# updi_programmer.net
KiCad netlist of a schematic drawn in EAGLE
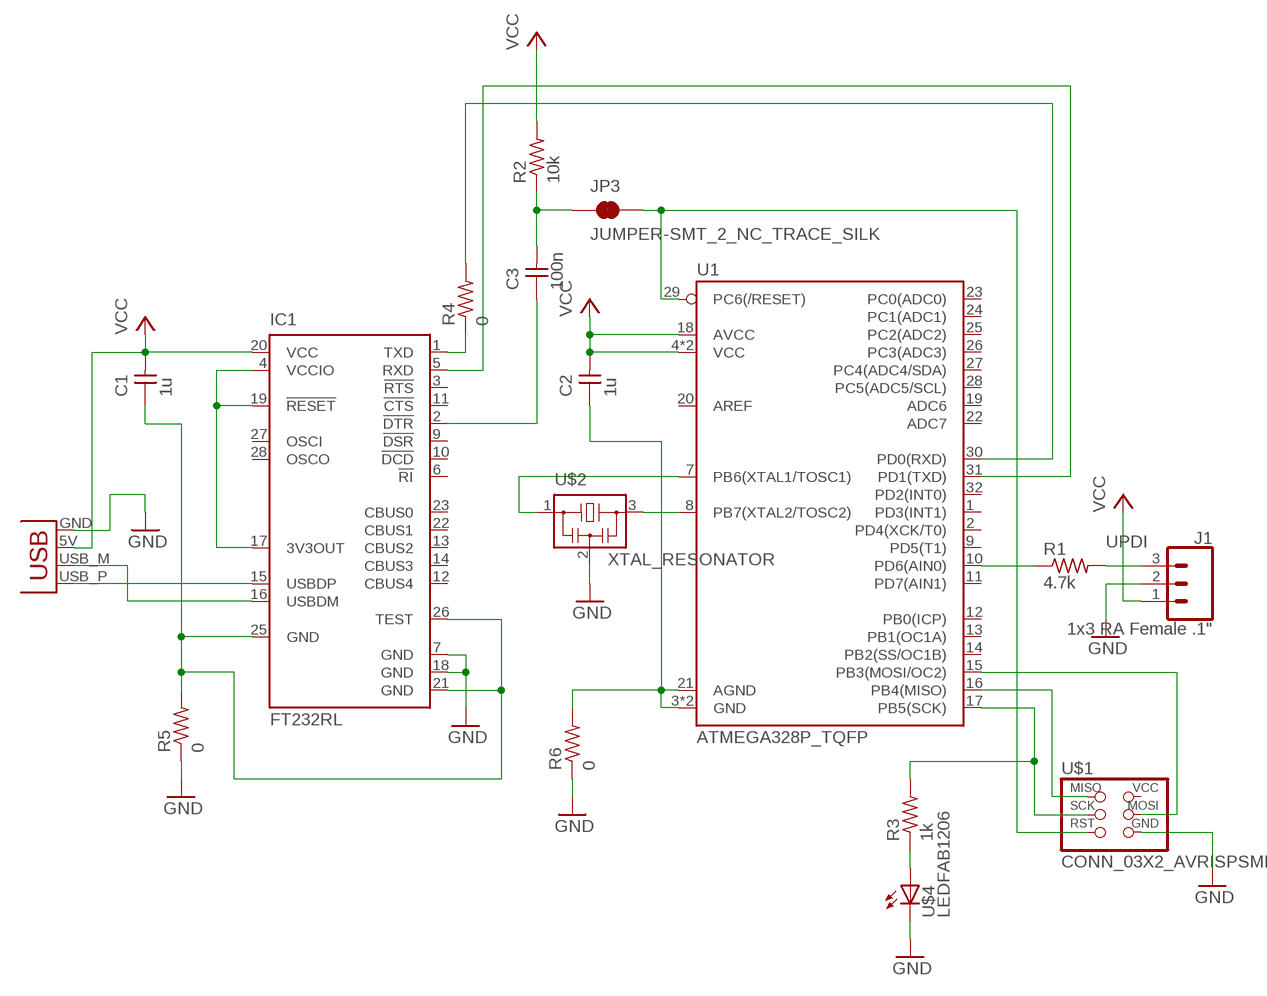
[diagram p0: schematic, sheet 1]

(export (version "E")
  (design (tool "Eeschema 10.0.6"))
  (components
    (comp (ref "C1")
      (value "1u")
      (footprint "eagle-import:C1206FAB")
      (libsource (lib "eagle-import") (part "CAP_UNPOLARIZEDFAB"))
    )
    (comp (ref "C2")
      (value "1u")
      (footprint "eagle-import:C1206FAB")
      (libsource (lib "eagle-import") (part "CAP_UNPOLARIZEDFAB"))
    )
    (comp (ref "C3")
      (value "100n")
      (footprint "eagle-import:C1206FAB")
      (libsource (lib "eagle-import") (part "CAP_UNPOLARIZEDFAB"))
    )
    (comp (ref "IC1")
      (value "FT232RL")
      (footprint "eagle-import:SSOP28")
      (libsource (lib "eagle-import") (part "FT232RL"))
    )
    (comp (ref "J1")
      (value "1x3 RA Female .1\"")
      (footprint "eagle-import:1X03_SMD_RA_FEMALE")
      (libsource (lib "eagle-import") (part "CONN_03SMD_RA_FEMALE"))
    )
    (comp (ref "JP3")
      (value "JUMPER-SMT_2_NC_TRACE_SILK")
      (footprint "eagle-import:SMT-JUMPER_2_NC_TRACE_SILK")
      (libsource (lib "eagle-import") (part "JUMPER-SMT_2_NC_TRACE_SILK"))
    )
    (comp (ref "R1")
      (value "4.7k")
      (footprint "eagle-import:R1206FAB")
      (libsource (lib "eagle-import") (part "R1206FAB"))
    )
    (comp (ref "R2")
      (value "10k")
      (footprint "eagle-import:R1206FAB")
      (libsource (lib "eagle-import") (part "R1206FAB"))
    )
    (comp (ref "R3")
      (value "1k")
      (footprint "eagle-import:R1206FAB")
      (libsource (lib "eagle-import") (part "R1206FAB"))
    )
    (comp (ref "R4")
      (value "0")
      (footprint "eagle-import:R1206FAB")
      (libsource (lib "eagle-import") (part "R1206FAB"))
    )
    (comp (ref "R5")
      (value "0")
      (footprint "eagle-import:R1206FAB")
      (libsource (lib "eagle-import") (part "R1206FAB"))
    )
    (comp (ref "R6")
      (value "0")
      (footprint "eagle-import:R1206FAB")
      (libsource (lib "eagle-import") (part "R1206FAB"))
    )
    (comp (ref "U$1")
      (value "CONN_03X2_AVRISPSMD")
      (footprint "eagle-import:2X03SMD")
      (libsource (lib "eagle-import") (part "CONN_03X2_AVRISPSMD"))
    )
    (comp (ref "U$2")
      (value "XTAL_RESONATOR")
      (footprint "eagle-import:EFOBM")
      (libsource (lib "eagle-import") (part "XTAL_RESONATOR"))
    )
    (comp (ref "U$4")
      (value "LEDFAB1206")
      (footprint "eagle-import:LED1206FAB")
      (libsource (lib "eagle-import") (part "LEDFAB1206"))
    )
    (comp (ref "U1")
      (value "ATMEGA328P_TQFP")
      (footprint "eagle-import:TQFP32-08")
      (libsource (lib "eagle-import") (part "ATMEGA328P_TQFP"))
    )
    (comp (ref "X1")
      (value "CONN_USBPCB")
      (footprint "eagle-import:USB-A-PCB")
      (libsource (lib "eagle-import") (part "CONN_USBPCB"))
    )
  )
  (nets
    (net (code "1") (name "/UPDI") (class "Default")
      (node (ref "J1") (pin "3") (pinfunction "3_3") (pintype "passive"))
      (node (ref "R1") (pin "2") (pinfunction "2_2") (pintype "passive"))
    )
    (net (code "2") (name "GND") (class "Default")
      (node (ref "IC1") (pin "18") (pinfunction "GND_18") (pintype "power_in"))
      (node (ref "IC1") (pin "7") (pinfunction "GND_7") (pintype "power_in"))
      (node (ref "J1") (pin "2") (pinfunction "2_2") (pintype "passive"))
      (node (ref "R5") (pin "1") (pinfunction "1_1") (pintype "passive"))
      (node (ref "R6") (pin "1") (pinfunction "1_1") (pintype "passive"))
      (node (ref "U$1") (pin "6") (pinfunction "GND_6") (pintype "passive"))
      (node (ref "U$2") (pin "2") (pinfunction "2_2") (pintype "passive"))
      (node (ref "U$4") (pin "2") (pinfunction "C_2") (pintype "passive"))
      (node (ref "X1") (pin "GND") (pinfunction "GND_GND") (pintype "bidirectional"))
    )
    (net (code "3") (name "Net-(C3-Pad2)") (class "Default")
      (node (ref "C3") (pin "2") (pinfunction "2_2") (pintype "passive"))
      (node (ref "JP3") (pin "1") (pinfunction "1_1") (pintype "passive"))
      (node (ref "R2") (pin "1") (pinfunction "1_1") (pintype "passive"))
    )
    (net (code "4") (name "Net-(IC1-3V3OUT)") (class "Default")
      (node (ref "IC1") (pin "17") (pinfunction "3V3OUT_17") (pintype "output"))
      (node (ref "IC1") (pin "19") (pinfunction "~{RESET}_19") (pintype "input"))
      (node (ref "IC1") (pin "4") (pinfunction "VCCIO_4") (pintype "power_in"))
    )
    (net (code "5") (name "Net-(IC1-RXD)") (class "Default")
      (node (ref "IC1") (pin "5") (pinfunction "RXD_5") (pintype "input"))
      (node (ref "U1") (pin "31") (pinfunction "PD1(TXD)_31") (pintype "bidirectional"))
    )
    (net (code "6") (name "Net-(IC1-TEST)") (class "Default")
      (node (ref "C1") (pin "1") (pinfunction "1_1") (pintype "passive"))
      (node (ref "IC1") (pin "21") (pinfunction "GND_21") (pintype "power_in"))
      (node (ref "IC1") (pin "25") (pinfunction "GND_25") (pintype "power_in"))
      (node (ref "IC1") (pin "26") (pinfunction "TEST_26") (pintype "input"))
      (node (ref "R5") (pin "2") (pinfunction "2_2") (pintype "passive"))
    )
    (net (code "7") (name "Net-(IC1-TXD)") (class "Default")
      (node (ref "IC1") (pin "1") (pinfunction "TXD_1") (pintype "output"))
      (node (ref "R4") (pin "1") (pinfunction "1_1") (pintype "passive"))
    )
    (net (code "8") (name "Net-(IC1-USBDM)") (class "Default")
      (node (ref "IC1") (pin "16") (pinfunction "USBDM_16") (pintype "bidirectional"))
      (node (ref "X1") (pin "USB_M") (pinfunction "D-_USB_M") (pintype "bidirectional"))
    )
    (net (code "9") (name "Net-(IC1-USBDP)") (class "Default")
      (node (ref "IC1") (pin "15") (pinfunction "USBDP_15") (pintype "bidirectional"))
      (node (ref "X1") (pin "USB_P") (pinfunction "D+_USB_P") (pintype "bidirectional"))
    )
    (net (code "10") (name "Net-(IC1-~{DTR})") (class "Default")
      (node (ref "C3") (pin "1") (pinfunction "1_1") (pintype "passive"))
      (node (ref "IC1") (pin "2") (pinfunction "~{DTR}_2") (pintype "output"))
    )
    (net (code "11") (name "Net-(U$1-MISO)") (class "Default")
      (node (ref "U$1") (pin "1") (pinfunction "MISO_1") (pintype "passive"))
      (node (ref "U1") (pin "16") (pinfunction "PB4(MISO)_16") (pintype "bidirectional"))
    )
    (net (code "12") (name "Net-(U$1-MOSI)") (class "Default")
      (node (ref "U$1") (pin "4") (pinfunction "MOSI_4") (pintype "passive"))
      (node (ref "U1") (pin "15") (pinfunction "PB3(MOSI/OC2)_15") (pintype "bidirectional"))
    )
    (net (code "13") (name "Net-(U$1-RST)") (class "Default")
      (node (ref "JP3") (pin "2") (pinfunction "2_2") (pintype "passive"))
      (node (ref "U$1") (pin "5") (pinfunction "RST_5") (pintype "passive"))
      (node (ref "U1") (pin "29") (pinfunction "PC6(/RESET)_29") (pintype "bidirectional"))
    )
    (net (code "14") (name "Net-(U$1-SCK)") (class "Default")
      (node (ref "R3") (pin "2") (pinfunction "2_2") (pintype "passive"))
      (node (ref "U$1") (pin "3") (pinfunction "SCK_3") (pintype "passive"))
      (node (ref "U1") (pin "17") (pinfunction "PB5(SCK)_17") (pintype "bidirectional"))
    )
    (net (code "15") (name "Net-(U$4-A)") (class "Default")
      (node (ref "R3") (pin "1") (pinfunction "1_1") (pintype "passive"))
      (node (ref "U$4") (pin "1") (pinfunction "A_1") (pintype "passive"))
    )
    (net (code "16") (name "Net-(U1-AGND)") (class "Default")
      (node (ref "C2") (pin "1") (pinfunction "1_1") (pintype "passive"))
      (node (ref "R6") (pin "2") (pinfunction "2_2") (pintype "passive"))
      (node (ref "U1") (pin "21") (pinfunction "AGND_21") (pintype "bidirectional"))
      (node (ref "U1") (pin "3") (pinfunction "GND_3") (pintype "bidirectional"))
      (node (ref "U1") (pin "5") (pinfunction "GND_5") (pintype "bidirectional"))
    )
    (net (code "17") (name "Net-(U1-PB6(XTAL1{slash}TOSC1))") (class "Default")
      (node (ref "U$2") (pin "1") (pinfunction "1_1") (pintype "passive"))
      (node (ref "U1") (pin "7") (pinfunction "PB6(XTAL1/TOSC1)_7") (pintype "bidirectional"))
    )
    (net (code "18") (name "Net-(U1-PB7(XTAL2{slash}TOSC2))") (class "Default")
      (node (ref "U$2") (pin "3") (pinfunction "3_3") (pintype "passive"))
      (node (ref "U1") (pin "8") (pinfunction "PB7(XTAL2/TOSC2)_8") (pintype "bidirectional"))
    )
    (net (code "19") (name "Net-(U1-PD0(RXD))") (class "Default")
      (node (ref "R4") (pin "2") (pinfunction "2_2") (pintype "passive"))
      (node (ref "U1") (pin "30") (pinfunction "PD0(RXD)_30") (pintype "bidirectional"))
    )
    (net (code "20") (name "Net-(U1-PD6(AIN0))") (class "Default")
      (node (ref "R1") (pin "1") (pinfunction "1_1") (pintype "passive"))
      (node (ref "U1") (pin "10") (pinfunction "PD6(AIN0)_10") (pintype "bidirectional"))
    )
    (net (code "21") (name "VCC") (class "Default")
      (node (ref "C1") (pin "2") (pinfunction "2_2") (pintype "passive"))
      (node (ref "C2") (pin "2") (pinfunction "2_2") (pintype "passive"))
      (node (ref "IC1") (pin "20") (pinfunction "VCC_20") (pintype "power_in"))
      (node (ref "J1") (pin "1") (pinfunction "1_1") (pintype "passive"))
      (node (ref "R2") (pin "2") (pinfunction "2_2") (pintype "passive"))
      (node (ref "U1") (pin "18") (pinfunction "AVCC_18") (pintype "bidirectional"))
      (node (ref "U1") (pin "4") (pinfunction "VCC_4") (pintype "bidirectional"))
      (node (ref "U1") (pin "6") (pinfunction "VCC_6") (pintype "bidirectional"))
      (node (ref "X1") (pin "5V") (pinfunction "VBUS_5V") (pintype "bidirectional"))
    )
    (net (code "22") (name "unconnected-(IC1-CBUS0-Pad23)") (class "Default")
      (node (ref "IC1") (pin "23") (pinfunction "CBUS0_23") (pintype "bidirectional"))
    )
    (net (code "23") (name "unconnected-(IC1-CBUS1-Pad22)") (class "Default")
      (node (ref "IC1") (pin "22") (pinfunction "CBUS1_22") (pintype "bidirectional"))
    )
    (net (code "24") (name "unconnected-(IC1-CBUS2-Pad13)") (class "Default")
      (node (ref "IC1") (pin "13") (pinfunction "CBUS2_13") (pintype "bidirectional"))
    )
    (net (code "25") (name "unconnected-(IC1-CBUS3-Pad14)") (class "Default")
      (node (ref "IC1") (pin "14") (pinfunction "CBUS3_14") (pintype "bidirectional"))
    )
    (net (code "26") (name "unconnected-(IC1-CBUS4-Pad12)") (class "Default")
      (node (ref "IC1") (pin "12") (pinfunction "CBUS4_12") (pintype "bidirectional"))
    )
    (net (code "27") (name "unconnected-(IC1-OSCI-Pad27)") (class "Default")
      (node (ref "IC1") (pin "27") (pinfunction "OSCI_27") (pintype "input"))
    )
    (net (code "28") (name "unconnected-(IC1-OSCO-Pad28)") (class "Default")
      (node (ref "IC1") (pin "28") (pinfunction "OSCO_28") (pintype "output"))
    )
    (net (code "29") (name "unconnected-(IC1-~{CTS}-Pad11)") (class "Default")
      (node (ref "IC1") (pin "11") (pinfunction "~{CTS}_11") (pintype "input"))
    )
    (net (code "30") (name "unconnected-(IC1-~{DCD}-Pad10)") (class "Default")
      (node (ref "IC1") (pin "10") (pinfunction "~{DCD}_10") (pintype "input"))
    )
    (net (code "31") (name "unconnected-(IC1-~{DSR}-Pad9)") (class "Default")
      (node (ref "IC1") (pin "9") (pinfunction "~{DSR}_9") (pintype "input"))
    )
    (net (code "32") (name "unconnected-(IC1-~{RI}-Pad6)") (class "Default")
      (node (ref "IC1") (pin "6") (pinfunction "~{RI}_6") (pintype "input"))
    )
    (net (code "33") (name "unconnected-(IC1-~{RTS}-Pad3)") (class "Default")
      (node (ref "IC1") (pin "3") (pinfunction "~{RTS}_3") (pintype "output"))
    )
    (net (code "34") (name "unconnected-(U$1-VCC-Pad2)") (class "Default")
      (node (ref "U$1") (pin "2") (pinfunction "VCC_2") (pintype "passive"))
    )
    (net (code "35") (name "unconnected-(U1-ADC6-Pad19)") (class "Default")
      (node (ref "U1") (pin "19") (pinfunction "ADC6_19") (pintype "bidirectional"))
    )
    (net (code "36") (name "unconnected-(U1-ADC7-Pad22)") (class "Default")
      (node (ref "U1") (pin "22") (pinfunction "ADC7_22") (pintype "bidirectional"))
    )
    (net (code "37") (name "unconnected-(U1-AREF-Pad20)") (class "Default")
      (node (ref "U1") (pin "20") (pinfunction "AREF_20") (pintype "bidirectional"))
    )
    (net (code "38") (name "unconnected-(U1-PB0(ICP)-Pad12)") (class "Default")
      (node (ref "U1") (pin "12") (pinfunction "PB0(ICP)_12") (pintype "bidirectional"))
    )
    (net (code "39") (name "unconnected-(U1-PB1(OC1A)-Pad13)") (class "Default")
      (node (ref "U1") (pin "13") (pinfunction "PB1(OC1A)_13") (pintype "bidirectional"))
    )
    (net (code "40") (name "unconnected-(U1-PB2(SS{slash}OC1B)-Pad14)") (class "Default")
      (node (ref "U1") (pin "14") (pinfunction "PB2(SS/OC1B)_14") (pintype "bidirectional"))
    )
    (net (code "41") (name "unconnected-(U1-PC0(ADC0)-Pad23)") (class "Default")
      (node (ref "U1") (pin "23") (pinfunction "PC0(ADC0)_23") (pintype "bidirectional"))
    )
    (net (code "42") (name "unconnected-(U1-PC1(ADC1)-Pad24)") (class "Default")
      (node (ref "U1") (pin "24") (pinfunction "PC1(ADC1)_24") (pintype "bidirectional"))
    )
    (net (code "43") (name "unconnected-(U1-PC2(ADC2)-Pad25)") (class "Default")
      (node (ref "U1") (pin "25") (pinfunction "PC2(ADC2)_25") (pintype "bidirectional"))
    )
    (net (code "44") (name "unconnected-(U1-PC3(ADC3)-Pad26)") (class "Default")
      (node (ref "U1") (pin "26") (pinfunction "PC3(ADC3)_26") (pintype "bidirectional"))
    )
    (net (code "45") (name "unconnected-(U1-PC4(ADC4{slash}SDA)-Pad27)") (class "Default")
      (node (ref "U1") (pin "27") (pinfunction "PC4(ADC4/SDA)_27") (pintype "bidirectional"))
    )
    (net (code "46") (name "unconnected-(U1-PC5(ADC5{slash}SCL)-Pad28)") (class "Default")
      (node (ref "U1") (pin "28") (pinfunction "PC5(ADC5/SCL)_28") (pintype "bidirectional"))
    )
    (net (code "47") (name "unconnected-(U1-PD2(INT0)-Pad32)") (class "Default")
      (node (ref "U1") (pin "32") (pinfunction "PD2(INT0)_32") (pintype "bidirectional"))
    )
    (net (code "48") (name "unconnected-(U1-PD3(INT1)-Pad1)") (class "Default")
      (node (ref "U1") (pin "1") (pinfunction "PD3(INT1)_1") (pintype "bidirectional"))
    )
    (net (code "49") (name "unconnected-(U1-PD4(XCK{slash}T0)-Pad2)") (class "Default")
      (node (ref "U1") (pin "2") (pinfunction "PD4(XCK/T0)_2") (pintype "bidirectional"))
    )
    (net (code "50") (name "unconnected-(U1-PD5(T1)-Pad9)") (class "Default")
      (node (ref "U1") (pin "9") (pinfunction "PD5(T1)_9") (pintype "bidirectional"))
    )
    (net (code "51") (name "unconnected-(U1-PD7(AIN1)-Pad11)") (class "Default")
      (node (ref "U1") (pin "11") (pinfunction "PD7(AIN1)_11") (pintype "bidirectional"))
    )
  )
)
